# V_4.net
KiCad netlist of a schematic drawn in Altium Designer
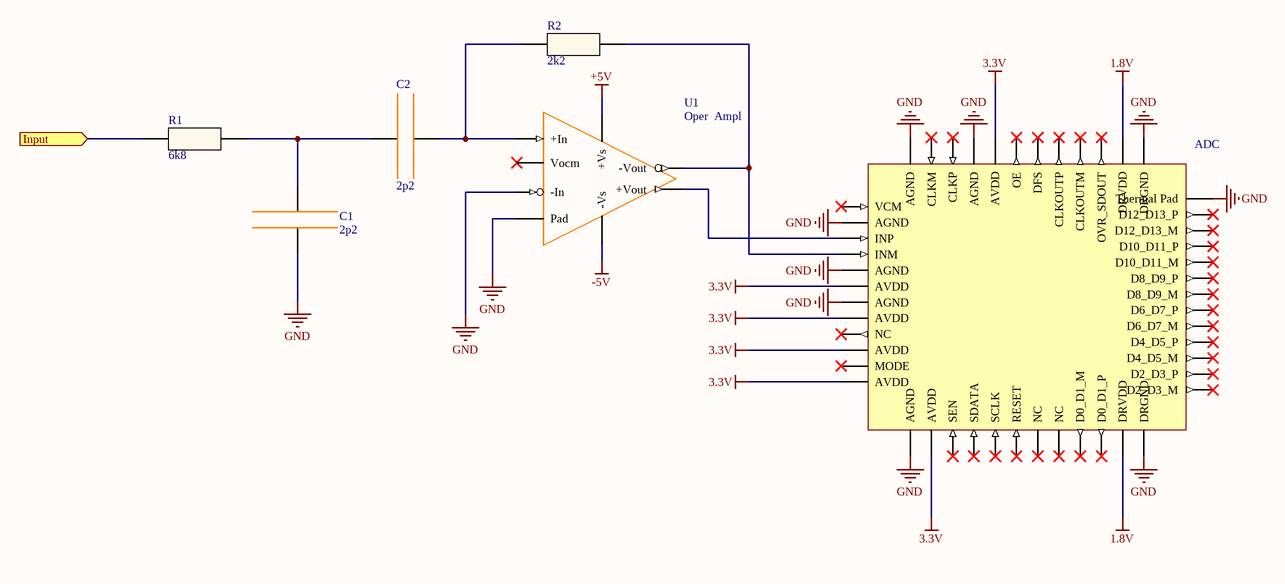
[diagram p0: V_4.SchDoc]

(export (version "E")
  (design (tool "Eeschema 10.0.6"))
  (components
    (comp (ref "C1") (value "2p2") (footprint "C0805") (libsource (lib "V_4") (part "Capasitor")))
    (comp (ref "C2") (value "2p2") (footprint "C0805") (libsource (lib "") (part "Capasitor_1")))
    (comp (ref "R1")
      (value "6k8")
      (footprint "R0805")
      (libsource (lib "altium-import") (part "root_0_Resistor_"))
    )
    (comp (ref "R2") (value "2k2") (footprint "R0805") (libsource (lib "V_4") (part "Resistor")))
    (comp (ref "U1") (value "Oper  Ampl") (footprint "ADA") (libsource (lib "V_4") (part "Oper  Ampl")))
    (comp (ref "U2") (value "ADC") (footprint "ADS") (libsource (lib "V4") (part "ADC")))
  )
  (nets
    (net (code "1") (name "+5V") (class "Default")
      (node (ref "U1") (pin "23") (pinfunction "+Vs_23") (pintype "passive"))
    )
    (net (code "2") (name "-5V") (class "Default")
      (node (ref "U1") (pin "22") (pinfunction "-Vs_22") (pintype "passive"))
    )
    (net (code "3") (name "/Input") (class "Default")
      (node (ref "R1") (pin "0") (pinfunction "0_0") (pintype "passive"))
    )
    (net (code "4") (name "1.8V") (class "Default")
      (node (ref "U2") (pin "27") (pinfunction "DRVDD_27") (pintype "power_in"))
      (node (ref "U2") (pin "60") (pinfunction "DRVDD_60") (pintype "power_in"))
    )
    (net (code "5") (name "3.3V") (class "Default")
      (node (ref "U2") (pin "33") (pinfunction "AVDD_33") (pintype "power_in"))
      (node (ref "U2") (pin "43") (pinfunction "AVDD_43") (pintype "power_in"))
      (node (ref "U2") (pin "45") (pinfunction "AVDD_45") (pintype "power_in"))
      (node (ref "U2") (pin "47") (pinfunction "AVDD_47") (pintype "power_in"))
      (node (ref "U2") (pin "49") (pinfunction "AVDD_49") (pintype "power_in"))
      (node (ref "U2") (pin "51") (pinfunction "AVDD_51") (pintype "power_in"))
    )
    (net (code "6") (name "GND") (class "Default")
      (node (ref "C1") (pin "3") (pinfunction "3_3") (pintype "passive"))
      (node (ref "U1") (pin "20") (pinfunction "-In_20") (pintype "input"))
      (node (ref "U1") (pin "21") (pinfunction "Pad_21") (pintype "passive"))
      (node (ref "U2") (pin "26") (pinfunction "DRGND_26") (pintype "power_in"))
      (node (ref "U2") (pin "34") (pinfunction "AGND_34") (pintype "power_in"))
      (node (ref "U2") (pin "37") (pinfunction "AGND_37") (pintype "power_in"))
      (node (ref "U2") (pin "39") (pinfunction "AGND_39") (pintype "power_in"))
      (node (ref "U2") (pin "42") (pinfunction "AGND_42") (pintype "power_in"))
      (node (ref "U2") (pin "44") (pinfunction "AGND_44") (pintype "power_in"))
      (node (ref "U2") (pin "50") (pinfunction "AGND_50") (pintype "power_in"))
      (node (ref "U2") (pin "61") (pinfunction "DRGND_61") (pintype "power_in"))
      (node (ref "U2") (pin "74") (pinfunction "Thermal_Pad_74") (pintype "power_in"))
    )
    (net (code "7") (name "Net-(C1-Pad3)") (class "Default")
      (node (ref "C1") (pin "3") (pinfunction "3_3") (pintype "passive"))
      (node (ref "C2") (pin "2") (pinfunction "2_2") (pintype "passive"))
      (node (ref "R1") (pin "1") (pinfunction "1_1") (pintype "passive"))
    )
    (net (code "8") (name "Net-(U1-+In)") (class "Default")
      (node (ref "C2") (pin "3") (pinfunction "3_3") (pintype "passive"))
      (node (ref "R2") (pin "0") (pinfunction "0_0") (pintype "passive"))
      (node (ref "U1") (pin "18") (pinfunction "+In_18") (pintype "input"))
    )
    (net (code "9") (name "Net-(U1-+Vout)") (class "Default")
      (node (ref "U1") (pin "25") (pinfunction "+Vout_25") (pintype "output"))
      (node (ref "U2") (pin "40") (pinfunction "INP_40") (pintype "input"))
    )
    (net (code "10") (name "Net-(U1--Vout)") (class "Default")
      (node (ref "R2") (pin "1") (pinfunction "1_1") (pintype "passive"))
      (node (ref "U1") (pin "24") (pinfunction "-Vout_24") (pintype "output"))
      (node (ref "U2") (pin "41") (pinfunction "INM_41") (pintype "input"))
    )
    (net (code "11") (name "unconnected-(U1-Vocm-Pad19)") (class "Default")
      (node (ref "U1") (pin "19") (pinfunction "Vocm_19") (pintype "passive+no_connect"))
    )
    (net (code "12") (name "unconnected-(U2-CLKM-Pad36)") (class "Default")
      (node (ref "U2") (pin "36") (pinfunction "CLKM_36") (pintype "input+no_connect"))
    )
    (net (code "13") (name "unconnected-(U2-CLKOUTM-Pad29)") (class "Default")
      (node (ref "U2") (pin "29") (pinfunction "CLKOUTM_29") (pintype "output+no_connect"))
    )
    (net (code "14") (name "unconnected-(U2-CLKOUTP-Pad30)") (class "Default")
      (node (ref "U2") (pin "30") (pinfunction "CLKOUTP_30") (pintype "output+no_connect"))
    )
    (net (code "15") (name "unconnected-(U2-CLKP-Pad35)") (class "Default")
      (node (ref "U2") (pin "35") (pinfunction "CLKP_35") (pintype "input+no_connect"))
    )
    (net (code "16") (name "unconnected-(U2-D0_D1_M-Pad58)") (class "Default")
      (node (ref "U2") (pin "58") (pinfunction "D0_D1_M_58") (pintype "output+no_connect"))
    )
    (net (code "17") (name "unconnected-(U2-D0_D1_P-Pad59)") (class "Default")
      (node (ref "U2") (pin "59") (pinfunction "D0_D1_P_59") (pintype "output+no_connect"))
    )
    (net (code "18") (name "unconnected-(U2-D2_D3_M-Pad62)") (class "Default")
      (node (ref "U2") (pin "62") (pinfunction "D2_D3_M_62") (pintype "output+no_connect"))
    )
    (net (code "19") (name "unconnected-(U2-D2_D3_P-Pad63)") (class "Default")
      (node (ref "U2") (pin "63") (pinfunction "D2_D3_P_63") (pintype "output+no_connect"))
    )
    (net (code "20") (name "unconnected-(U2-D4_D5_M-Pad64)") (class "Default")
      (node (ref "U2") (pin "64") (pinfunction "D4_D5_M_64") (pintype "output+no_connect"))
    )
    (net (code "21") (name "unconnected-(U2-D4_D5_P-Pad65)") (class "Default")
      (node (ref "U2") (pin "65") (pinfunction "D4_D5_P_65") (pintype "output+no_connect"))
    )
    (net (code "22") (name "unconnected-(U2-D6_D7_M-Pad66)") (class "Default")
      (node (ref "U2") (pin "66") (pinfunction "D6_D7_M_66") (pintype "output+no_connect"))
    )
    (net (code "23") (name "unconnected-(U2-D6_D7_P-Pad67)") (class "Default")
      (node (ref "U2") (pin "67") (pinfunction "D6_D7_P_67") (pintype "output+no_connect"))
    )
    (net (code "24") (name "unconnected-(U2-D8_D9_M-Pad68)") (class "Default")
      (node (ref "U2") (pin "68") (pinfunction "D8_D9_M_68") (pintype "output+no_connect"))
    )
    (net (code "25") (name "unconnected-(U2-D8_D9_P-Pad69)") (class "Default")
      (node (ref "U2") (pin "69") (pinfunction "D8_D9_P_69") (pintype "output+no_connect"))
    )
    (net (code "26") (name "unconnected-(U2-D10_D11_M-Pad70)") (class "Default")
      (node (ref "U2") (pin "70") (pinfunction "D10_D11_M_70") (pintype "output+no_connect"))
    )
    (net (code "27") (name "unconnected-(U2-D10_D11_P-Pad71)") (class "Default")
      (node (ref "U2") (pin "71") (pinfunction "D10_D11_P_71") (pintype "output+no_connect"))
    )
    (net (code "28") (name "unconnected-(U2-D12_D13_M-Pad72)") (class "Default")
      (node (ref "U2") (pin "72") (pinfunction "D12_D13_M_72") (pintype "output+no_connect"))
    )
    (net (code "29") (name "unconnected-(U2-D12_D13_P-Pad73)") (class "Default")
      (node (ref "U2") (pin "73") (pinfunction "D12_D13_P_73") (pintype "output+no_connect"))
    )
    (net (code "30") (name "unconnected-(U2-DFS-Pad31)") (class "Default")
      (node (ref "U2") (pin "31") (pinfunction "DFS_31") (pintype "output+no_connect"))
    )
    (net (code "31") (name "unconnected-(U2-MODE-Pad48)") (class "Default")
      (node (ref "U2") (pin "48") (pinfunction "MODE_48") (pintype "power_in+no_connect"))
    )
    (net (code "32") (name "unconnected-(U2-NC-Pad46)") (class "Default")
      (node (ref "U2") (pin "46") (pinfunction "NC_46") (pintype "output+no_connect"))
    )
    (net (code "33") (name "unconnected-(U2-NC-Pad56)") (class "Default")
      (node (ref "U2") (pin "56") (pinfunction "NC_56") (pintype "power_in+no_connect"))
    )
    (net (code "34") (name "unconnected-(U2-NC-Pad57)") (class "Default")
      (node (ref "U2") (pin "57") (pinfunction "NC_57") (pintype "power_in+no_connect"))
    )
    (net (code "35") (name "unconnected-(U2-OE-Pad32)") (class "Default")
      (node (ref "U2") (pin "32") (pinfunction "OE_32") (pintype "output+no_connect"))
    )
    (net (code "36") (name "unconnected-(U2-OVR_SDOUT-Pad28)") (class "Default")
      (node (ref "U2") (pin "28") (pinfunction "OVR_SDOUT_28") (pintype "output+no_connect"))
    )
    (net (code "37") (name "unconnected-(U2-RESET-Pad55)") (class "Default")
      (node (ref "U2") (pin "55") (pinfunction "RESET_55") (pintype "input+no_connect"))
    )
    (net (code "38") (name "unconnected-(U2-SCLK-Pad54)") (class "Default")
      (node (ref "U2") (pin "54") (pinfunction "SCLK_54") (pintype "input+no_connect"))
    )
    (net (code "39") (name "unconnected-(U2-SDATA-Pad53)") (class "Default")
      (node (ref "U2") (pin "53") (pinfunction "SDATA_53") (pintype "input+no_connect"))
    )
    (net (code "40") (name "unconnected-(U2-SEN-Pad52)") (class "Default")
      (node (ref "U2") (pin "52") (pinfunction "SEN_52") (pintype "input+no_connect"))
    )
    (net (code "41") (name "unconnected-(U2-VCM-Pad38)") (class "Default")
      (node (ref "U2") (pin "38") (pinfunction "VCM_38") (pintype "input+no_connect"))
    )
  )
)
